# USB.net
KiCad netlist of a schematic drawn in Altium Designer
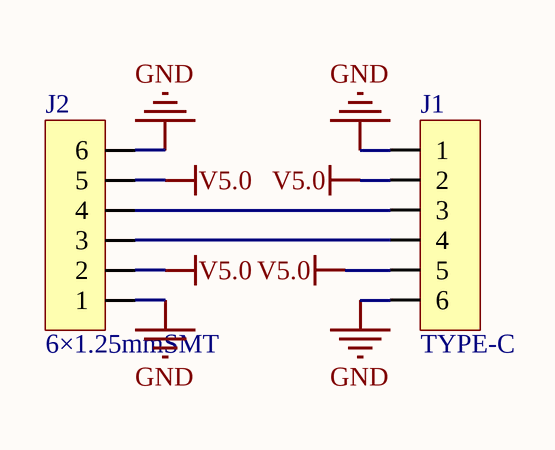
[diagram p0: USB.SchDoc]

(export (version "E")
  (design (tool "Eeschema 10.0.6"))
  (components
    (comp (ref "J1")
      (value "TYPE-C")
      (footprint "USB-TYPE-C-6P")
      (description "USB 3.1 Type-C 2.0短体母座 6P贴片式")
      (libsource (lib "XiaoyI") (part "SIP-6"))
    )
    (comp (ref "J2")
      (value "6×1.25mmSMT")
      (footprint "6×1.25mmSMT")
      (description "USB 3.1 Type-C 2.0短体母座 6P贴片式")
      (libsource (lib "") (part "SIP-6_1"))
    )
  )
  (nets
    (net (code "1") (name "GND") (class "Default")
      (node (ref "J1") (pin "1") (pinfunction "1_1") (pintype "passive"))
      (node (ref "J1") (pin "6") (pinfunction "6_6") (pintype "passive"))
      (node (ref "J2") (pin "1") (pinfunction "1_1") (pintype "passive"))
      (node (ref "J2") (pin "6") (pinfunction "6_6") (pintype "passive"))
    )
    (net (code "2") (name "Net-(J1-Pad3)") (class "Default")
      (node (ref "J1") (pin "3") (pinfunction "3_3") (pintype "passive"))
      (node (ref "J2") (pin "4") (pinfunction "4_4") (pintype "passive"))
    )
    (net (code "3") (name "Net-(J1-Pad4)") (class "Default")
      (node (ref "J1") (pin "4") (pinfunction "4_4") (pintype "passive"))
      (node (ref "J2") (pin "3") (pinfunction "3_3") (pintype "passive"))
    )
    (net (code "4") (name "V5.0") (class "Default")
      (node (ref "J1") (pin "2") (pinfunction "2_2") (pintype "passive"))
      (node (ref "J1") (pin "5") (pinfunction "5_5") (pintype "passive"))
      (node (ref "J2") (pin "2") (pinfunction "2_2") (pintype "passive"))
      (node (ref "J2") (pin "5") (pinfunction "5_5") (pintype "passive"))
    )
  )
)
